# Maxim_7219_LED_display_-_Sparkfun_YoungS.net
KiCad netlist of a schematic drawn in EAGLE
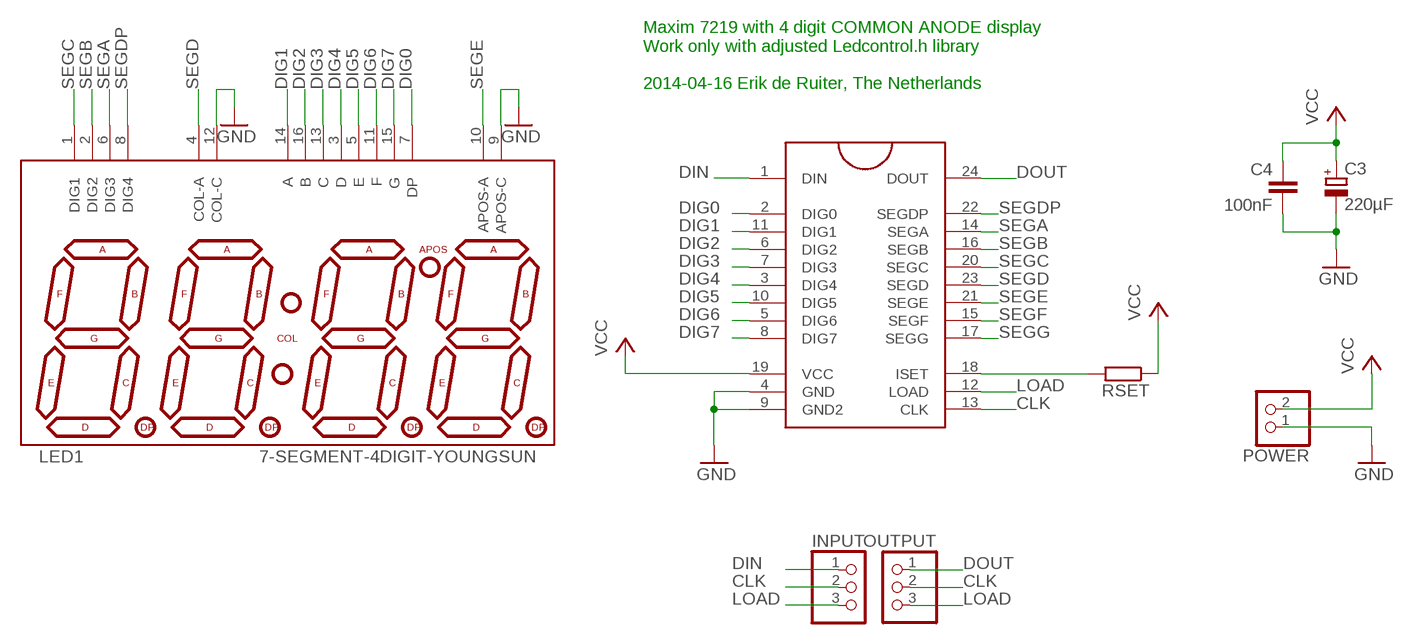
[diagram p0: schematic, sheet 1]

(export (version "E")
  (design (tool "Eeschema 10.0.6"))
  (components
    (comp (ref "C3")
      (value "220µF")
      (footprint "eagle-import:E3,5-8")
      (libsource (lib "eagle-import") (part "CPOL-EUE3.5-8"))
    )
    (comp (ref "C4")
      (value "100nF")
      (footprint "eagle-import:C050-025X075")
      (libsource (lib "eagle-import") (part "C-EU050-025X075"))
    )
    (comp (ref "INPUT")
      (value "PINHD-1X3")
      (footprint "eagle-import:1X03")
      (libsource (lib "eagle-import") (part "PINHD-1X3"))
    )
    (comp (ref "LED1")
      (value "7-SEGMENT-4DIGIT-YOUNGSUN")
      (footprint "eagle-import:7-SEGMENT-4DIGIT-YOUNGSUN")
      (libsource (lib "eagle-import") (part "7-SEGMENT-4DIGIT-YOUNGSUN"))
    )
    (comp (ref "OUTPUT")
      (value "PINHD-1X3")
      (footprint "eagle-import:1X03")
      (libsource (lib "eagle-import") (part "PINHD-1X3"))
    )
    (comp (ref "POWER")
      (value "PINHD-1X2")
      (footprint "eagle-import:1X02")
      (libsource (lib "eagle-import") (part "PINHD-1X2"))
    )
    (comp (ref "RSET")
      (value "R-EU_0207/10")
      (footprint "eagle-import:0207_10")
      (libsource (lib "eagle-import") (part "R-EU_0207/10"))
    )
    (comp (ref "U$3")
      (value "MAX7219DIP")
      (footprint "eagle-import:DIL24")
      (libsource (lib "eagle-import") (part "MAX7219DIP"))
    )
  )
  (nets
    (net (code "1") (name "/CLK") (class "Default")
      (node (ref "INPUT") (pin "2") (pinfunction "2_2") (pintype "passive"))
      (node (ref "OUTPUT") (pin "2") (pinfunction "2_2") (pintype "passive"))
      (node (ref "U$3") (pin "13") (pinfunction "CLK_13") (pintype "bidirectional"))
    )
    (net (code "2") (name "/DIG0") (class "Default")
      (node (ref "LED1") (pin "7") (pinfunction "DP_7") (pintype "bidirectional"))
      (node (ref "U$3") (pin "2") (pinfunction "DIG0_2") (pintype "bidirectional"))
    )
    (net (code "3") (name "/DIG1") (class "Default")
      (node (ref "LED1") (pin "14") (pinfunction "A_14") (pintype "bidirectional"))
      (node (ref "U$3") (pin "11") (pinfunction "DIG1_11") (pintype "bidirectional"))
    )
    (net (code "4") (name "/DIG2") (class "Default")
      (node (ref "LED1") (pin "16") (pinfunction "B_16") (pintype "bidirectional"))
      (node (ref "U$3") (pin "6") (pinfunction "DIG2_6") (pintype "bidirectional"))
    )
    (net (code "5") (name "/DIG3") (class "Default")
      (node (ref "LED1") (pin "13") (pinfunction "C_13") (pintype "bidirectional"))
      (node (ref "U$3") (pin "7") (pinfunction "DIG3_7") (pintype "bidirectional"))
    )
    (net (code "6") (name "/DIG4") (class "Default")
      (node (ref "LED1") (pin "3") (pinfunction "D_3") (pintype "bidirectional"))
      (node (ref "U$3") (pin "3") (pinfunction "DIG4_3") (pintype "bidirectional"))
    )
    (net (code "7") (name "/DIG5") (class "Default")
      (node (ref "LED1") (pin "5") (pinfunction "E_5") (pintype "bidirectional"))
      (node (ref "U$3") (pin "10") (pinfunction "DIG5_10") (pintype "bidirectional"))
    )
    (net (code "8") (name "/DIG6") (class "Default")
      (node (ref "LED1") (pin "11") (pinfunction "F_11") (pintype "bidirectional"))
      (node (ref "U$3") (pin "5") (pinfunction "DIG6_5") (pintype "bidirectional"))
    )
    (net (code "9") (name "/DIG7") (class "Default")
      (node (ref "LED1") (pin "15") (pinfunction "G_15") (pintype "bidirectional"))
      (node (ref "U$3") (pin "8") (pinfunction "DIG7_8") (pintype "bidirectional"))
    )
    (net (code "10") (name "/DIN") (class "Default")
      (node (ref "INPUT") (pin "1") (pinfunction "1_1") (pintype "passive"))
      (node (ref "U$3") (pin "1") (pinfunction "DIN_1") (pintype "bidirectional"))
    )
    (net (code "11") (name "/DOUT") (class "Default")
      (node (ref "OUTPUT") (pin "1") (pinfunction "1_1") (pintype "passive"))
      (node (ref "U$3") (pin "24") (pinfunction "DOUT_24") (pintype "bidirectional"))
    )
    (net (code "12") (name "/LOAD") (class "Default")
      (node (ref "INPUT") (pin "3") (pinfunction "3_3") (pintype "passive"))
      (node (ref "OUTPUT") (pin "3") (pinfunction "3_3") (pintype "passive"))
      (node (ref "U$3") (pin "12") (pinfunction "LOAD_12") (pintype "bidirectional"))
    )
    (net (code "13") (name "/SEGA") (class "Default")
      (node (ref "LED1") (pin "6") (pinfunction "DIG3_6") (pintype "bidirectional"))
      (node (ref "U$3") (pin "14") (pinfunction "SEGA_14") (pintype "bidirectional"))
    )
    (net (code "14") (name "/SEGB") (class "Default")
      (node (ref "LED1") (pin "2") (pinfunction "DIG2_2") (pintype "bidirectional"))
      (node (ref "U$3") (pin "16") (pinfunction "SEGB_16") (pintype "bidirectional"))
    )
    (net (code "15") (name "/SEGC") (class "Default")
      (node (ref "LED1") (pin "1") (pinfunction "DIG1_1") (pintype "bidirectional"))
      (node (ref "U$3") (pin "20") (pinfunction "SEGC_20") (pintype "bidirectional"))
    )
    (net (code "16") (name "/SEGD") (class "Default")
      (node (ref "LED1") (pin "4") (pinfunction "COL-A_4") (pintype "bidirectional"))
      (node (ref "U$3") (pin "23") (pinfunction "SEGD_23") (pintype "bidirectional"))
    )
    (net (code "17") (name "/SEGDP") (class "Default")
      (node (ref "LED1") (pin "8") (pinfunction "DIG4_8") (pintype "bidirectional"))
      (node (ref "U$3") (pin "22") (pinfunction "SEGDP_22") (pintype "bidirectional"))
    )
    (net (code "18") (name "/SEGE") (class "Default")
      (node (ref "LED1") (pin "10") (pinfunction "APOS-A_10") (pintype "bidirectional"))
      (node (ref "U$3") (pin "21") (pinfunction "SEGE_21") (pintype "bidirectional"))
    )
    (net (code "19") (name "/SEGF") (class "Default")
      (node (ref "U$3") (pin "15") (pinfunction "SEGF_15") (pintype "bidirectional"))
    )
    (net (code "20") (name "/SEGG") (class "Default")
      (node (ref "U$3") (pin "17") (pinfunction "SEGG_17") (pintype "bidirectional"))
    )
    (net (code "21") (name "GND") (class "Default")
      (node (ref "C3") (pin "-") (pinfunction "-_-") (pintype "passive"))
      (node (ref "C4") (pin "2") (pinfunction "2_2") (pintype "passive"))
      (node (ref "LED1") (pin "12") (pinfunction "COL-C_12") (pintype "bidirectional"))
      (node (ref "LED1") (pin "9") (pinfunction "APOS-C_9") (pintype "bidirectional"))
      (node (ref "POWER") (pin "1") (pinfunction "1_1") (pintype "passive"))
      (node (ref "U$3") (pin "4") (pinfunction "GND_4") (pintype "bidirectional"))
      (node (ref "U$3") (pin "9") (pinfunction "GND2_9") (pintype "bidirectional"))
    )
    (net (code "22") (name "Net-(U$3-ISET)") (class "Default")
      (node (ref "RSET") (pin "2") (pinfunction "2_2") (pintype "passive"))
      (node (ref "U$3") (pin "18") (pinfunction "ISET_18") (pintype "bidirectional"))
    )
    (net (code "23") (name "VCC") (class "Default")
      (node (ref "C3") (pin "+") (pinfunction "+_+") (pintype "passive"))
      (node (ref "C4") (pin "1") (pinfunction "1_1") (pintype "passive"))
      (node (ref "POWER") (pin "2") (pinfunction "2_2") (pintype "passive"))
      (node (ref "RSET") (pin "1") (pinfunction "1_1") (pintype "passive"))
      (node (ref "U$3") (pin "19") (pinfunction "VCC_19") (pintype "bidirectional"))
    )
  )
)
